# MCU.net
KiCad netlist of a schematic drawn in Altium Designer
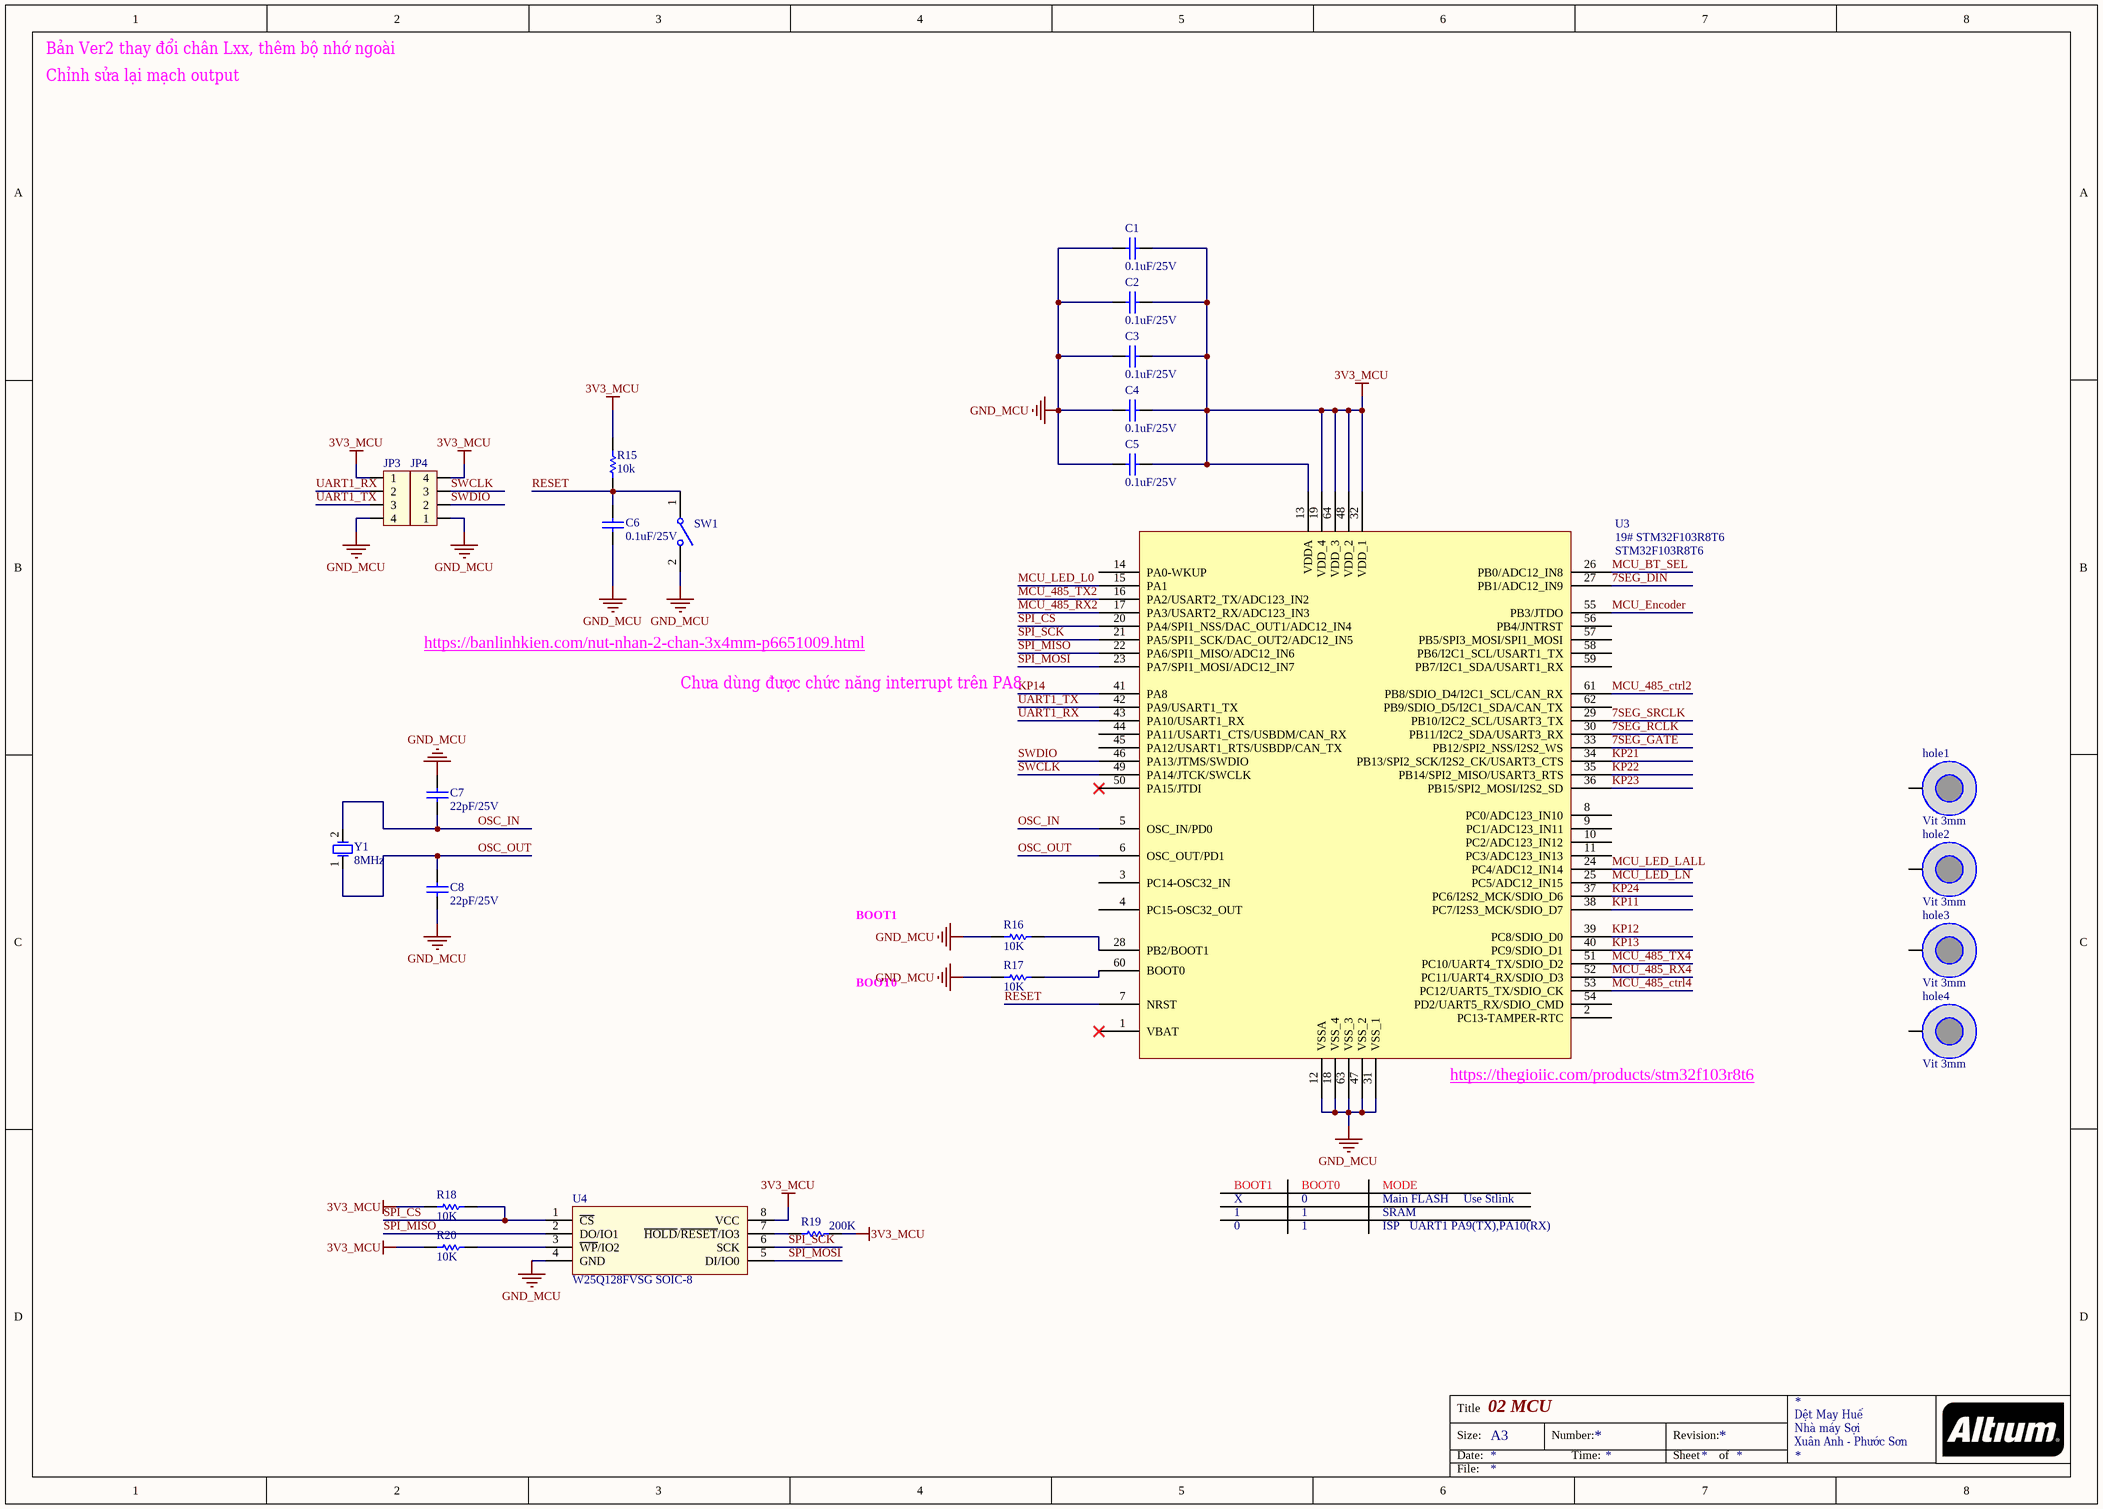
[diagram p0: MCU.SchDoc]

(export (version "E")
  (design (tool "Eeschema 10.0.6"))
  (components
    (comp (ref "C1")
      (value "0.1uF/25V")
      (footprint "Cap Ceramic 0805 SMD")
      (description "CAP CER 0.1UF 25V 10% X7R 0603")
      (fields
        (field (name "MANUFACTURER") "Murata Electronics North America")
        (field (name "MANUFACTURER PART NUMBER") "GRM188R71E104KA01D")
      )
      (libsource (lib "GSHT_181013") (part "0.1uF/25V/C0603/10%"))
    )
    (comp (ref "C2")
      (value "0.1uF/25V")
      (footprint "Cap Ceramic 0805 SMD")
      (description "CAP CER 0.1UF 25V 10% X7R 0603")
      (fields
        (field (name "MANUFACTURER") "Murata Electronics North America")
        (field (name "MANUFACTURER PART NUMBER") "GRM188R71E104KA01D")
      )
      (libsource (lib "GSHT_181013") (part "0.1uF/25V/C0603/10%"))
    )
    (comp (ref "C3")
      (value "0.1uF/25V")
      (footprint "Cap Ceramic 0805 SMD")
      (description "CAP CER 0.1UF 25V 10% X7R 0603")
      (fields
        (field (name "MANUFACTURER") "Murata Electronics North America")
        (field (name "MANUFACTURER PART NUMBER") "GRM188R71E104KA01D")
      )
      (libsource (lib "GSHT_181013") (part "0.1uF/25V/C0603/10%"))
    )
    (comp (ref "C4")
      (value "0.1uF/25V")
      (footprint "Cap Ceramic 0805 SMD")
      (description "CAP CER 0.1UF 25V 10% X7R 0603")
      (fields
        (field (name "MANUFACTURER") "Murata Electronics North America")
        (field (name "MANUFACTURER PART NUMBER") "GRM188R71E104KA01D")
      )
      (libsource (lib "GSHT_181013") (part "0.1uF/25V/C0603/10%"))
    )
    (comp (ref "C5")
      (value "0.1uF/25V")
      (footprint "Cap Ceramic 0805 SMD")
      (description "CAP CER 0.1UF 25V 10% X7R 0603")
      (fields
        (field (name "MANUFACTURER") "Murata Electronics North America")
        (field (name "MANUFACTURER PART NUMBER") "GRM188R71E104KA01D")
      )
      (libsource (lib "GSHT_181013") (part "0.1uF/25V/C0603/10%"))
    )
    (comp (ref "C6")
      (value "0.1uF/25V")
      (footprint "Cap Ceramic 0805 SMD")
      (description "CAP CER 0.1UF 25V 10% X7R 0603")
      (fields
        (field (name "MANUFACTURER") "Murata Electronics North America")
        (field (name "MANUFACTURER PART NUMBER") "GRM188R71E104KA01D")
      )
      (libsource (lib "GSHT_181013") (part "0.1uF/25V/C0603/10%"))
    )
    (comp (ref "C7")
      (value "22pF/25V")
      (footprint "Cap Ceramic 0805 SMD")
      (description "CAP CER 22PF 50V NP0 0603")
      (fields
        (field (name "MANUFACTURER") "Kemet")
        (field (name "MANUFACTURER PART NUMBER") "C0603C220K5GACTU")
      )
      (libsource (lib "GSHT_181013") (part "22pF/50V/C0603/10%"))
    )
    (comp (ref "C8")
      (value "22pF/25V")
      (footprint "Cap Ceramic 0805 SMD")
      (description "CAP CER 22PF 50V NP0 0603")
      (fields
        (field (name "MANUFACTURER") "Kemet")
        (field (name "MANUFACTURER PART NUMBER") "C0603C220K5GACTU")
      )
      (libsource (lib "GSHT_181013") (part "22pF/50V/C0603/10%"))
    )
    (comp (ref "hole1")
      (value "Vit 3mm")
      (footprint "Screw 3 small")
      (libsource (lib "lpson") (part "Vit 3mm"))
    )
    (comp (ref "hole2")
      (value "Vit 3mm")
      (footprint "Screw 3 small")
      (libsource (lib "lpson") (part "Vit 3mm"))
    )
    (comp (ref "hole3")
      (value "Vit 3mm")
      (footprint "Screw 3 small")
      (libsource (lib "lpson") (part "Vit 3mm"))
    )
    (comp (ref "hole4")
      (value "Vit 3mm")
      (footprint "Screw 3 small")
      (libsource (lib "lpson") (part "Vit 3mm"))
    )
    (comp (ref "JP3")
      (value "PROGRAM")
      (footprint "Header_4")
      (description "Connector 4")
      (libsource (lib "") (part "Con4_1"))
    )
    (comp (ref "JP4")
      (value "PROGRAM")
      (footprint "Header_4")
      (description "Connector 4")
      (libsource (lib "lpson") (part "Con4"))
    )
    (comp (ref "R15")
      (value "10k")
      (footprint "Res 0805 SMD")
      (description "RES SMD 10K OHM 1% 1/10W 0603")
      (fields
        (field (name "MANUFACTURER") "Yageo")
        (field (name "MANUFACTURER PART NUMBER") "RC0603FR-0710KL")
      )
      (libsource (lib "GSHT_181013") (part "10K/R0603/1%"))
    )
    (comp (ref "R16")
      (value "10K")
      (footprint "Res 0805 SMD")
      (description "RES SMD 10K OHM 1% 1/10W 0603")
      (fields
        (field (name "MANUFACTURER") "Yageo")
        (field (name "MANUFACTURER PART NUMBER") "RC0603FR-0710KL")
      )
      (libsource (lib "GSHT_181013") (part "10K/R0603/1%"))
    )
    (comp (ref "R17")
      (value "10K")
      (footprint "Res 0805 SMD")
      (description "RES SMD 10K OHM 1% 1/10W 0603")
      (fields
        (field (name "MANUFACTURER") "Yageo")
        (field (name "MANUFACTURER PART NUMBER") "RC0603FR-0710KL")
      )
      (libsource (lib "GSHT_181013") (part "10K/R0603/1%"))
    )
    (comp (ref "R18")
      (value "10K")
      (footprint "Res 0805 SMD")
      (description "RES SMD 10K OHM 1% 1/10W 0603")
      (fields
        (field (name "MANUFACTURER") "Yageo")
        (field (name "MANUFACTURER PART NUMBER") "RC0603FR-0710KL")
      )
      (libsource (lib "GSHT_181013") (part "10K/R0603/1%"))
    )
    (comp (ref "R19")
      (value "200K")
      (footprint "Res 0805 SMD")
      (description "RES SMD 200K OHM 1% 1/10W 0603")
      (fields
        (field (name "MANUFACTURER") "Yageo")
        (field (name "MANUFACTURER PART NUMBER") "RC0603FR-07200KL")
      )
      (libsource (lib "GSHT_181013") (part "200K/R0603/1%"))
    )
    (comp (ref "R20")
      (value "10K")
      (footprint "Res 0805 SMD")
      (description "RES SMD 10K OHM 1% 1/10W 0603")
      (fields
        (field (name "MANUFACTURER") "Yageo")
        (field (name "MANUFACTURER PART NUMBER") "RC0603FR-0710KL")
      )
      (libsource (lib "GSHT_181013") (part "10K/R0603/1%"))
    )
    (comp (ref "SW1")
      (value "3x4x2.5 2Pin SMD")
      (footprint "Button 3x4mm")
      (fields
        (field (name "MANUFACTURER") "C&K Components")
        (field (name "MANUFACTURER PART NUMBER") "RS-282G05A3-SM RT")
      )
      (libsource (lib "GSHT_181013") (part "BUTTON 2-SMD RS-282G05A3"))
    )
    (comp (ref "U3")
      (value "19# STM32F103R8T6")
      (footprint "19# STMF103R8T6")
      (fields
        (field (name "SUPPLIER PART NUMBER 1") "STM32F103R8T6")
        (field (name "PUBLISHER") "Altium Limited")
      )
      (libsource (lib "GSHT_181013") (part "19# STM32F103R8T6"))
    )
    (comp (ref "U4")
      (value "W25Q128FVSG SOIC-8")
      (footprint "1# W25Q128FV - 8SOIC 5.38mm")
      (libsource (lib "GSHT_181013") (part "1# W25Q128FVSG SOIC-8"))
    )
    (comp (ref "Y1")
      (value "8MHz")
      (footprint "CRYSTAL SMD")
      (description "8MHz SMD")
      (libsource (lib "lpson") (part "Crystal SMD FA-128 26MHz"))
    )
  )
  (nets
    (net (code "1") (name "/7SEG_DIN") (class "Default")
      (node (ref "U3") (pin "27") (pinfunction "PB1/ADC12_IN9_27") (pintype "passive"))
    )
    (net (code "2") (name "/7SEG_GATE") (class "Default")
      (node (ref "U3") (pin "33") (pinfunction "PB12/SPI2_NSS/I2S2_WS_33") (pintype "passive"))
    )
    (net (code "3") (name "/7SEG_RCLK") (class "Default")
      (node (ref "U3") (pin "30") (pinfunction "PB11/I2C2_SDA/USART3_RX_30") (pintype "passive"))
    )
    (net (code "4") (name "/7SEG_SRCLK") (class "Default")
      (node (ref "U3") (pin "29") (pinfunction "PB10/I2C2_SCL/USART3_TX_29") (pintype "passive"))
    )
    (net (code "5") (name "/KP11") (class "Default")
      (node (ref "U3") (pin "38") (pinfunction "PC7/I2S3_MCK/SDIO_D7_38") (pintype "passive"))
    )
    (net (code "6") (name "/KP12") (class "Default")
      (node (ref "U3") (pin "39") (pinfunction "PC8/SDIO_D0_39") (pintype "passive"))
    )
    (net (code "7") (name "/KP13") (class "Default")
      (node (ref "U3") (pin "40") (pinfunction "PC9/SDIO_D1_40") (pintype "passive"))
    )
    (net (code "8") (name "/KP14") (class "Default")
      (node (ref "U3") (pin "41") (pinfunction "PA8_41") (pintype "passive"))
    )
    (net (code "9") (name "/KP21") (class "Default")
      (node (ref "U3") (pin "34") (pinfunction "PB13/SPI2_SCK/I2S2_CK/USART3_CTS_34") (pintype "passive"))
    )
    (net (code "10") (name "/KP22") (class "Default")
      (node (ref "U3") (pin "35") (pinfunction "PB14/SPI2_MISO/USART3_RTS_35") (pintype "passive"))
    )
    (net (code "11") (name "/KP23") (class "Default")
      (node (ref "U3") (pin "36") (pinfunction "PB15/SPI2_MOSI/I2S2_SD_36") (pintype "passive"))
    )
    (net (code "12") (name "/KP24") (class "Default")
      (node (ref "U3") (pin "37") (pinfunction "PC6/I2S2_MCK/SDIO_D6_37") (pintype "passive"))
    )
    (net (code "13") (name "/MCU_485_RX2") (class "Default")
      (node (ref "U3") (pin "17") (pinfunction "PA3/USART2_RX/ADC123_IN3_17") (pintype "passive"))
    )
    (net (code "14") (name "/MCU_485_RX4") (class "Default")
      (node (ref "U3") (pin "52") (pinfunction "PC11/UART4_RX/SDIO_D3_52") (pintype "passive"))
    )
    (net (code "15") (name "/MCU_485_TX2") (class "Default")
      (node (ref "U3") (pin "16") (pinfunction "PA2/USART2_TX/ADC123_IN2_16") (pintype "passive"))
    )
    (net (code "16") (name "/MCU_485_TX4") (class "Default")
      (node (ref "U3") (pin "51") (pinfunction "PC10/UART4_TX/SDIO_D2_51") (pintype "passive"))
    )
    (net (code "17") (name "/MCU_485_ctrl2") (class "Default")
      (node (ref "U3") (pin "61") (pinfunction "PB8/SDIO_D4/I2C1_SCL/CAN_RX_61") (pintype "passive"))
    )
    (net (code "18") (name "/MCU_485_ctrl4") (class "Default")
      (node (ref "U3") (pin "53") (pinfunction "PC12/UART5_TX/SDIO_CK_53") (pintype "passive"))
    )
    (net (code "19") (name "/MCU_BT_SEL") (class "Default")
      (node (ref "U3") (pin "26") (pinfunction "PB0/ADC12_IN8_26") (pintype "passive"))
    )
    (net (code "20") (name "/MCU_Encoder") (class "Default")
      (node (ref "U3") (pin "55") (pinfunction "PB3/JTDO_55") (pintype "passive"))
    )
    (net (code "21") (name "/MCU_LED_L0") (class "Default")
      (node (ref "U3") (pin "15") (pinfunction "PA1_15") (pintype "passive"))
    )
    (net (code "22") (name "/MCU_LED_LALL") (class "Default")
      (node (ref "U3") (pin "24") (pinfunction "PC4/ADC12_IN14_24") (pintype "passive"))
    )
    (net (code "23") (name "/MCU_LED_LN") (class "Default")
      (node (ref "U3") (pin "25") (pinfunction "PC5/ADC12_IN15_25") (pintype "passive"))
    )
    (net (code "24") (name "/OSC_IN") (class "Default")
      (node (ref "C7") (pin "2") (pinfunction "2_2") (pintype "passive"))
      (node (ref "U3") (pin "5") (pinfunction "OSC_IN/PD0_5") (pintype "passive"))
      (node (ref "Y1") (pin "2") (pinfunction "OSC2_2") (pintype "passive"))
    )
    (net (code "25") (name "/OSC_OUT") (class "Default")
      (node (ref "C8") (pin "1") (pinfunction "1_1") (pintype "passive"))
      (node (ref "U3") (pin "6") (pinfunction "OSC_OUT/PD1_6") (pintype "passive"))
      (node (ref "Y1") (pin "1") (pinfunction "OSC1_1") (pintype "passive"))
    )
    (net (code "26") (name "/RESET") (class "Default")
      (node (ref "C6") (pin "2") (pinfunction "2_2") (pintype "passive"))
      (node (ref "R15") (pin "1") (pinfunction "1_1") (pintype "passive"))
      (node (ref "SW1") (pin "1") (pinfunction "COMMON1_1") (pintype "passive"))
      (node (ref "U3") (pin "7") (pinfunction "NRST_7") (pintype "passive"))
    )
    (net (code "27") (name "/SPI_CS") (class "Default")
      (node (ref "R18") (pin "1") (pinfunction "1_1") (pintype "passive"))
      (node (ref "U3") (pin "20") (pinfunction "PA4/SPI1_NSS/DAC_OUT1/ADC12_IN4_20") (pintype "passive"))
      (node (ref "U4") (pin "1") (pinfunction "~{CS}_1") (pintype "passive"))
    )
    (net (code "28") (name "/SPI_MISO") (class "Default")
      (node (ref "U3") (pin "22") (pinfunction "PA6/SPI1_MISO/ADC12_IN6_22") (pintype "passive"))
      (node (ref "U4") (pin "2") (pinfunction "DO/IO1_2") (pintype "passive"))
    )
    (net (code "29") (name "/SPI_MOSI") (class "Default")
      (node (ref "U3") (pin "23") (pinfunction "PA7/SPI1_MOSI/ADC12_IN7_23") (pintype "passive"))
      (node (ref "U4") (pin "5") (pinfunction "DI/IO0_5") (pintype "passive"))
    )
    (net (code "30") (name "/SPI_SCK") (class "Default")
      (node (ref "U3") (pin "21") (pinfunction "PA5/SPI1_SCK/DAC_OUT2/ADC12_IN5_21") (pintype "passive"))
      (node (ref "U4") (pin "6") (pinfunction "SCK_6") (pintype "passive"))
    )
    (net (code "31") (name "/SWCLK") (class "Default")
      (node (ref "JP4") (pin "3") (pinfunction "3_3") (pintype "passive"))
      (node (ref "U3") (pin "49") (pinfunction "PA14/JTCK/SWCLK_49") (pintype "passive"))
    )
    (net (code "32") (name "/SWDIO") (class "Default")
      (node (ref "JP4") (pin "2") (pinfunction "2_2") (pintype "passive"))
      (node (ref "U3") (pin "46") (pinfunction "PA13/JTMS/SWDIO_46") (pintype "passive"))
    )
    (net (code "33") (name "/UART1_RX") (class "Default")
      (node (ref "JP3") (pin "2") (pinfunction "2_2") (pintype "passive"))
      (node (ref "U3") (pin "43") (pinfunction "PA10/USART1_RX_43") (pintype "passive"))
    )
    (net (code "34") (name "/UART1_TX") (class "Default")
      (node (ref "JP3") (pin "3") (pinfunction "3_3") (pintype "passive"))
      (node (ref "U3") (pin "42") (pinfunction "PA9/USART1_TX_42") (pintype "passive"))
    )
    (net (code "35") (name "3V3_MCU") (class "Default")
      (node (ref "C1") (pin "2") (pinfunction "2_2") (pintype "passive"))
      (node (ref "C2") (pin "2") (pinfunction "2_2") (pintype "passive"))
      (node (ref "C3") (pin "2") (pinfunction "2_2") (pintype "passive"))
      (node (ref "C4") (pin "2") (pinfunction "2_2") (pintype "passive"))
      (node (ref "C5") (pin "2") (pinfunction "2_2") (pintype "passive"))
      (node (ref "JP3") (pin "1") (pinfunction "1_1") (pintype "passive"))
      (node (ref "JP4") (pin "4") (pinfunction "4_4") (pintype "passive"))
      (node (ref "R15") (pin "2") (pinfunction "2_2") (pintype "passive"))
      (node (ref "R18") (pin "2") (pinfunction "2_2") (pintype "passive"))
      (node (ref "R19") (pin "1") (pinfunction "1_1") (pintype "passive"))
      (node (ref "R20") (pin "1") (pinfunction "1_1") (pintype "passive"))
      (node (ref "U3") (pin "13") (pinfunction "VDDA_13") (pintype "power_in"))
      (node (ref "U3") (pin "19") (pinfunction "VDD_4_19") (pintype "power_in"))
      (node (ref "U3") (pin "32") (pinfunction "VDD_1_32") (pintype "power_in"))
      (node (ref "U3") (pin "48") (pinfunction "VDD_2_48") (pintype "power_in"))
      (node (ref "U3") (pin "64") (pinfunction "VDD_3_64") (pintype "power_in"))
      (node (ref "U4") (pin "8") (pinfunction "VCC_8") (pintype "passive"))
    )
    (net (code "36") (name "GND_MCU") (class "Default")
      (node (ref "C1") (pin "1") (pinfunction "1_1") (pintype "passive"))
      (node (ref "C2") (pin "1") (pinfunction "1_1") (pintype "passive"))
      (node (ref "C3") (pin "1") (pinfunction "1_1") (pintype "passive"))
      (node (ref "C4") (pin "1") (pinfunction "1_1") (pintype "passive"))
      (node (ref "C5") (pin "1") (pinfunction "1_1") (pintype "passive"))
      (node (ref "C6") (pin "1") (pinfunction "1_1") (pintype "passive"))
      (node (ref "C7") (pin "1") (pinfunction "1_1") (pintype "passive"))
      (node (ref "C8") (pin "2") (pinfunction "2_2") (pintype "passive"))
      (node (ref "JP3") (pin "4") (pinfunction "4_4") (pintype "passive"))
      (node (ref "JP4") (pin "1") (pinfunction "1_1") (pintype "passive"))
      (node (ref "R16") (pin "2") (pinfunction "2_2") (pintype "passive"))
      (node (ref "R17") (pin "1") (pinfunction "1_1") (pintype "passive"))
      (node (ref "SW1") (pin "2") (pinfunction "NO1_2") (pintype "passive"))
      (node (ref "U3") (pin "12") (pinfunction "VSSA_12") (pintype "power_in"))
      (node (ref "U3") (pin "18") (pinfunction "VSS_4_18") (pintype "power_in"))
      (node (ref "U3") (pin "31") (pinfunction "VSS_1_31") (pintype "power_in"))
      (node (ref "U3") (pin "47") (pinfunction "VSS_2_47") (pintype "power_in"))
      (node (ref "U3") (pin "63") (pinfunction "VSS_3_63") (pintype "power_in"))
      (node (ref "U4") (pin "4") (pinfunction "GND_4") (pintype "passive"))
    )
    (net (code "37") (name "Net-(U3-BOOT0)") (class "Default")
      (node (ref "R17") (pin "2") (pinfunction "2_2") (pintype "passive"))
      (node (ref "U3") (pin "60") (pinfunction "BOOT0_60") (pintype "passive"))
    )
    (net (code "38") (name "Net-(U3-PB2{slash}BOOT1)") (class "Default")
      (node (ref "R16") (pin "1") (pinfunction "1_1") (pintype "passive"))
      (node (ref "U3") (pin "28") (pinfunction "PB2/BOOT1_28") (pintype "passive"))
    )
    (net (code "39") (name "Net-(U4-~{HOLD}{slash}~{RESET}{slash}IO3)") (class "Default")
      (node (ref "R19") (pin "2") (pinfunction "2_2") (pintype "passive"))
      (node (ref "U4") (pin "7") (pinfunction "~{HOLD}/~{RESET}/IO3_7") (pintype "passive"))
    )
    (net (code "40") (name "Net-(U4-~{WP}{slash}IO2)") (class "Default")
      (node (ref "R20") (pin "2") (pinfunction "2_2") (pintype "passive"))
      (node (ref "U4") (pin "3") (pinfunction "~{WP}/IO2_3") (pintype "passive"))
    )
    (net (code "41") (name "unconnected-(U3-PA0-WKUP-Pad14)") (class "Default")
      (node (ref "U3") (pin "14") (pinfunction "PA0-WKUP_14") (pintype "passive"))
    )
    (net (code "42") (name "unconnected-(U3-PA11{slash}USART1_CTS{slash}USBDM{slash}CAN_RX-Pad44)") (class "Default")
      (node (ref "U3") (pin "44") (pinfunction "PA11/USART1_CTS/USBDM/CAN_RX_44") (pintype "passive"))
    )
    (net (code "43") (name "unconnected-(U3-PA12{slash}USART1_RTS{slash}USBDP{slash}CAN_TX-Pad45)") (class "Default")
      (node (ref "U3") (pin "45") (pinfunction "PA12/USART1_RTS/USBDP/CAN_TX_45") (pintype "passive"))
    )
    (net (code "44") (name "unconnected-(U3-PA15{slash}JTDI-Pad50)") (class "Default")
      (node (ref "U3") (pin "50") (pinfunction "PA15/JTDI_50") (pintype "passive+no_connect"))
    )
    (net (code "45") (name "unconnected-(U3-PB4{slash}JNTRST-Pad56)") (class "Default")
      (node (ref "U3") (pin "56") (pinfunction "PB4/JNTRST_56") (pintype "passive"))
    )
    (net (code "46") (name "unconnected-(U3-PB5{slash}SPI3_MOSI{slash}SPI1_MOSI-Pad57)") (class "Default")
      (node (ref "U3") (pin "57") (pinfunction "PB5/SPI3_MOSI/SPI1_MOSI_57") (pintype "passive"))
    )
    (net (code "47") (name "unconnected-(U3-PB6{slash}I2C1_SCL{slash}USART1_TX-Pad58)") (class "Default")
      (node (ref "U3") (pin "58") (pinfunction "PB6/I2C1_SCL/USART1_TX_58") (pintype "passive"))
    )
    (net (code "48") (name "unconnected-(U3-PB7{slash}I2C1_SDA{slash}USART1_RX-Pad59)") (class "Default")
      (node (ref "U3") (pin "59") (pinfunction "PB7/I2C1_SDA/USART1_RX_59") (pintype "passive"))
    )
    (net (code "49") (name "unconnected-(U3-PB9{slash}SDIO_D5{slash}I2C1_SDA{slash}CAN_TX-Pad62)") (class "Default")
      (node (ref "U3") (pin "62") (pinfunction "PB9/SDIO_D5/I2C1_SDA/CAN_TX_62") (pintype "passive"))
    )
    (net (code "50") (name "unconnected-(U3-PC0{slash}ADC123_IN10-Pad8)") (class "Default")
      (node (ref "U3") (pin "8") (pinfunction "PC0/ADC123_IN10_8") (pintype "passive"))
    )
    (net (code "51") (name "unconnected-(U3-PC1{slash}ADC123_IN11-Pad9)") (class "Default")
      (node (ref "U3") (pin "9") (pinfunction "PC1/ADC123_IN11_9") (pintype "passive"))
    )
    (net (code "52") (name "unconnected-(U3-PC2{slash}ADC123_IN12-Pad10)") (class "Default")
      (node (ref "U3") (pin "10") (pinfunction "PC2/ADC123_IN12_10") (pintype "passive"))
    )
    (net (code "53") (name "unconnected-(U3-PC3{slash}ADC123_IN13-Pad11)") (class "Default")
      (node (ref "U3") (pin "11") (pinfunction "PC3/ADC123_IN13_11") (pintype "passive"))
    )
    (net (code "54") (name "unconnected-(U3-PC13-TAMPER-RTC-Pad2)") (class "Default")
      (node (ref "U3") (pin "2") (pinfunction "PC13-TAMPER-RTC_2") (pintype "passive"))
    )
    (net (code "55") (name "unconnected-(U3-PC14-OSC32_IN-Pad3)") (class "Default")
      (node (ref "U3") (pin "3") (pinfunction "PC14-OSC32_IN_3") (pintype "passive"))
    )
    (net (code "56") (name "unconnected-(U3-PC15-OSC32_OUT-Pad4)") (class "Default")
      (node (ref "U3") (pin "4") (pinfunction "PC15-OSC32_OUT_4") (pintype "passive"))
    )
    (net (code "57") (name "unconnected-(U3-PD2{slash}UART5_RX{slash}SDIO_CMD-Pad54)") (class "Default")
      (node (ref "U3") (pin "54") (pinfunction "PD2/UART5_RX/SDIO_CMD_54") (pintype "passive"))
    )
    (net (code "58") (name "unconnected-(U3-VBAT-Pad1)") (class "Default")
      (node (ref "U3") (pin "1") (pinfunction "VBAT_1") (pintype "power_in+no_connect"))
    )
    (net (code "59") (name "unconnected-(hole1-hole-Pad1)") (class "Default")
      (node (ref "hole1") (pin "1") (pinfunction "hole_1") (pintype "passive"))
    )
    (net (code "60") (name "unconnected-(hole2-hole-Pad1)") (class "Default")
      (node (ref "hole2") (pin "1") (pinfunction "hole_1") (pintype "passive"))
    )
    (net (code "61") (name "unconnected-(hole3-hole-Pad1)") (class "Default")
      (node (ref "hole3") (pin "1") (pinfunction "hole_1") (pintype "passive"))
    )
    (net (code "62") (name "unconnected-(hole4-hole-Pad1)") (class "Default")
      (node (ref "hole4") (pin "1") (pinfunction "hole_1") (pintype "passive"))
    )
  )
)
